# memory.net
KiCad netlist of a schematic drawn in Altium Designer
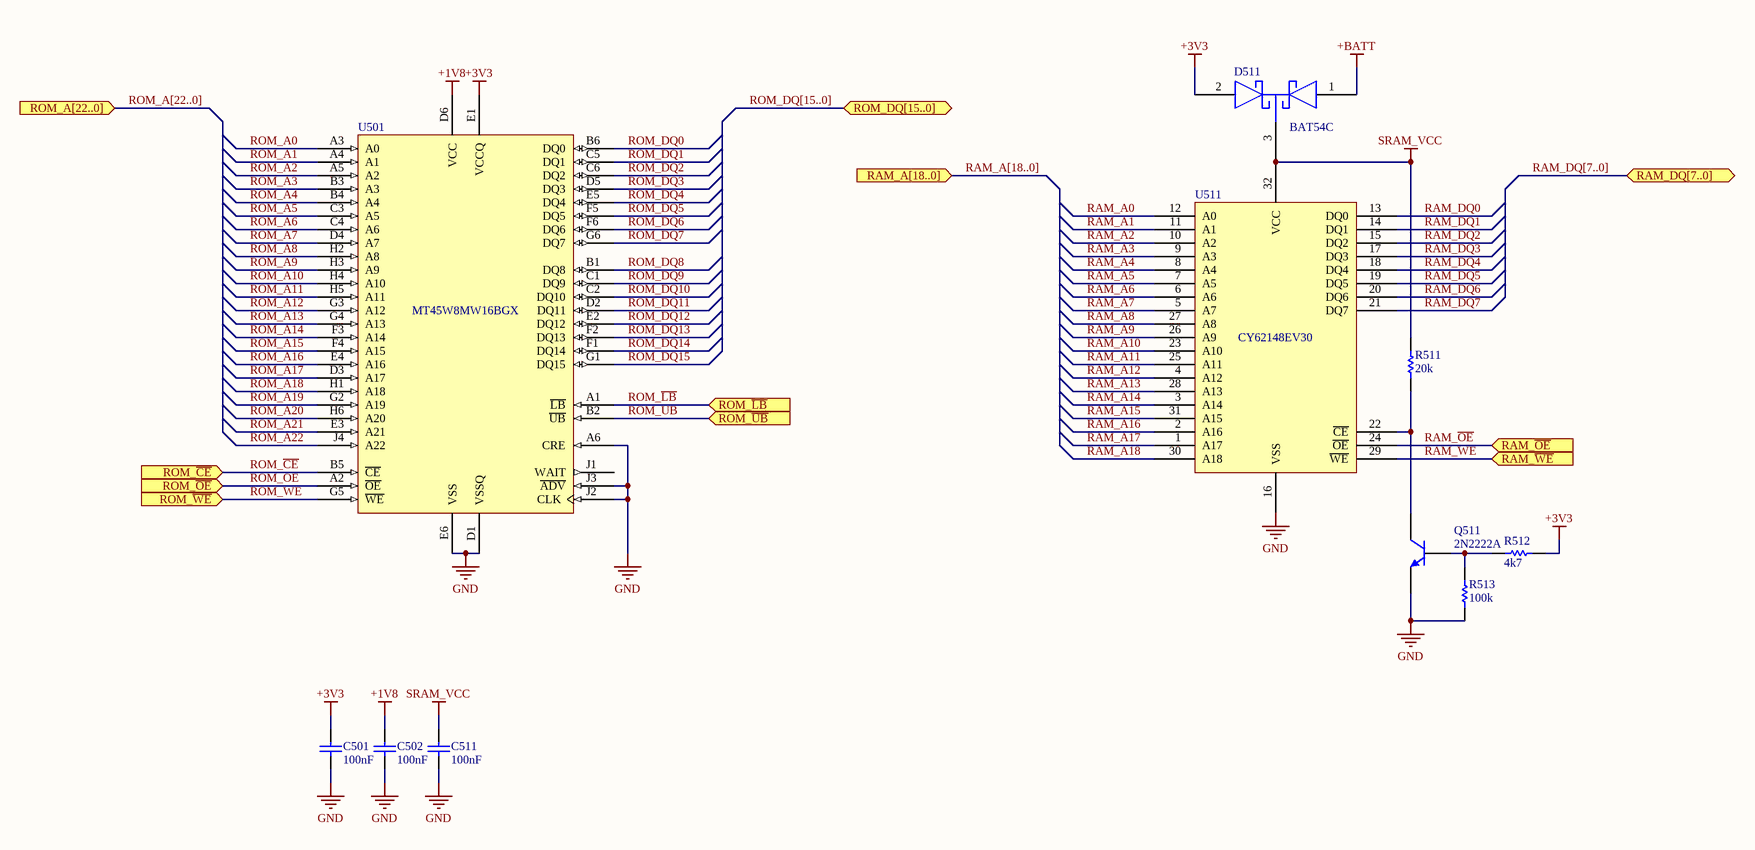
[diagram p0: memory.SchDoc]

(export (version "E")
  (design (tool "Eeschema 10.0.6"))
  (components
    (comp (ref "C501")
      (value "100nF")
      (footprint "SM0805")
      (description "Capacitor")
      (libsource (lib "Miscellaneous Devices") (part "Cap"))
    )
    (comp (ref "C502")
      (value "100nF")
      (footprint "SM0805")
      (description "Capacitor")
      (libsource (lib "Miscellaneous Devices") (part "Cap"))
    )
    (comp (ref "C511")
      (value "100nF")
      (footprint "SM0805")
      (description "Capacitor")
      (libsource (lib "Miscellaneous Devices") (part "Cap"))
    )
    (comp (ref "D511") (value "BAT54C") (footprint "SOT23EBC") (libsource (lib "Schlib1") (part "BAT54C")))
    (comp (ref "Q511")
      (value "2N2222A")
      (footprint "SOT23EBC")
      (description "NPN Transistor")
      (libsource (lib "Schlib1") (part "NPN"))
    )
    (comp (ref "R511")
      (value "20k")
      (footprint "SM0805")
      (description "Resistor")
      (libsource (lib "Miscellaneous Devices") (part "Res1"))
    )
    (comp (ref "R512")
      (value "4k7")
      (footprint "SM0805")
      (description "Resistor")
      (libsource (lib "Miscellaneous Devices") (part "Res1"))
    )
    (comp (ref "R513")
      (value "100k")
      (footprint "SM0805")
      (description "Resistor")
      (libsource (lib "Miscellaneous Devices") (part "Res1"))
    )
    (comp (ref "U501")
      (value "MT45W8MW16BGX")
      (footprint "VFBGA54")
      (libsource (lib "Schlib1") (part "MT45W8MW16BGX"))
    )
    (comp (ref "U511")
      (value "CY62148EV30")
      (footprint "TSOPII-32")
      (libsource (lib "Schlib1") (part "CY62148EV30"))
    )
  )
  (nets
    (net (code "1") (name "+1V8") (class "Default")
      (node (ref "C502") (pin "1") (pinfunction "1_1") (pintype "passive"))
      (node (ref "U501") (pin "D6") (pinfunction "VCC_D6") (pintype "power_in"))
    )
    (net (code "2") (name "+3V3") (class "Default")
      (node (ref "C501") (pin "1") (pinfunction "1_1") (pintype "passive"))
      (node (ref "D511") (pin "2") (pinfunction "2_2") (pintype "passive"))
      (node (ref "R512") (pin "2") (pinfunction "2_2") (pintype "passive"))
      (node (ref "U501") (pin "E1") (pinfunction "VCCQ_E1") (pintype "power_in"))
    )
    (net (code "3") (name "+BATT") (class "Default")
      (node (ref "D511") (pin "1") (pinfunction "1_1") (pintype "passive"))
    )
    (net (code "4") (name "/RAM_A0") (class "Default")
      (node (ref "U511") (pin "12") (pinfunction "A0_12") (pintype "passive"))
    )
    (net (code "5") (name "/RAM_A1") (class "Default")
      (node (ref "U511") (pin "11") (pinfunction "A1_11") (pintype "passive"))
    )
    (net (code "6") (name "/RAM_A2") (class "Default")
      (node (ref "U511") (pin "10") (pinfunction "A2_10") (pintype "passive"))
    )
    (net (code "7") (name "/RAM_A3") (class "Default")
      (node (ref "U511") (pin "9") (pinfunction "A3_9") (pintype "passive"))
    )
    (net (code "8") (name "/RAM_A4") (class "Default")
      (node (ref "U511") (pin "8") (pinfunction "A4_8") (pintype "passive"))
    )
    (net (code "9") (name "/RAM_A5") (class "Default")
      (node (ref "U511") (pin "7") (pinfunction "A5_7") (pintype "passive"))
    )
    (net (code "10") (name "/RAM_A6") (class "Default")
      (node (ref "U511") (pin "6") (pinfunction "A6_6") (pintype "passive"))
    )
    (net (code "11") (name "/RAM_A7") (class "Default")
      (node (ref "U511") (pin "5") (pinfunction "A7_5") (pintype "passive"))
    )
    (net (code "12") (name "/RAM_A8") (class "Default")
      (node (ref "U511") (pin "27") (pinfunction "A8_27") (pintype "passive"))
    )
    (net (code "13") (name "/RAM_A9") (class "Default")
      (node (ref "U511") (pin "26") (pinfunction "A9_26") (pintype "passive"))
    )
    (net (code "14") (name "/RAM_A10") (class "Default")
      (node (ref "U511") (pin "23") (pinfunction "A10_23") (pintype "passive"))
    )
    (net (code "15") (name "/RAM_A11") (class "Default")
      (node (ref "U511") (pin "25") (pinfunction "A11_25") (pintype "passive"))
    )
    (net (code "16") (name "/RAM_A12") (class "Default")
      (node (ref "U511") (pin "4") (pinfunction "A12_4") (pintype "passive"))
    )
    (net (code "17") (name "/RAM_A13") (class "Default")
      (node (ref "U511") (pin "28") (pinfunction "A13_28") (pintype "passive"))
    )
    (net (code "18") (name "/RAM_A14") (class "Default")
      (node (ref "U511") (pin "3") (pinfunction "A14_3") (pintype "passive"))
    )
    (net (code "19") (name "/RAM_A15") (class "Default")
      (node (ref "U511") (pin "31") (pinfunction "A15_31") (pintype "passive"))
    )
    (net (code "20") (name "/RAM_A16") (class "Default")
      (node (ref "U511") (pin "2") (pinfunction "A16_2") (pintype "passive"))
    )
    (net (code "21") (name "/RAM_A17") (class "Default")
      (node (ref "U511") (pin "1") (pinfunction "A17_1") (pintype "passive"))
    )
    (net (code "22") (name "/RAM_A18") (class "Default")
      (node (ref "U511") (pin "30") (pinfunction "A18_30") (pintype "passive"))
    )
    (net (code "24") (name "/RAM_DQ0") (class "Default")
      (node (ref "U511") (pin "13") (pinfunction "DQ0_13") (pintype "passive"))
    )
    (net (code "25") (name "/RAM_DQ1") (class "Default")
      (node (ref "U511") (pin "14") (pinfunction "DQ1_14") (pintype "passive"))
    )
    (net (code "26") (name "/RAM_DQ2") (class "Default")
      (node (ref "U511") (pin "15") (pinfunction "DQ2_15") (pintype "passive"))
    )
    (net (code "27") (name "/RAM_DQ3") (class "Default")
      (node (ref "U511") (pin "17") (pinfunction "DQ3_17") (pintype "passive"))
    )
    (net (code "28") (name "/RAM_DQ4") (class "Default")
      (node (ref "U511") (pin "18") (pinfunction "DQ4_18") (pintype "passive"))
    )
    (net (code "29") (name "/RAM_DQ5") (class "Default")
      (node (ref "U511") (pin "19") (pinfunction "DQ5_19") (pintype "passive"))
    )
    (net (code "30") (name "/RAM_DQ6") (class "Default")
      (node (ref "U511") (pin "20") (pinfunction "DQ6_20") (pintype "passive"))
    )
    (net (code "31") (name "/RAM_DQ7") (class "Default")
      (node (ref "U511") (pin "21") (pinfunction "DQ7_21") (pintype "passive"))
    )
    (net (code "33") (name "/RAM_~{OE}") (class "Default")
      (node (ref "U511") (pin "24") (pinfunction "~{OE}_24") (pintype "passive"))
    )
    (net (code "34") (name "/RAM_~{WE}") (class "Default")
      (node (ref "U511") (pin "29") (pinfunction "~{WE}_29") (pintype "passive"))
    )
    (net (code "35") (name "/ROM_A0") (class "Default")
      (node (ref "U501") (pin "A3") (pinfunction "A0_A3") (pintype "input"))
    )
    (net (code "36") (name "/ROM_A1") (class "Default")
      (node (ref "U501") (pin "A4") (pinfunction "A1_A4") (pintype "input"))
    )
    (net (code "37") (name "/ROM_A2") (class "Default")
      (node (ref "U501") (pin "A5") (pinfunction "A2_A5") (pintype "input"))
    )
    (net (code "38") (name "/ROM_A3") (class "Default")
      (node (ref "U501") (pin "B3") (pinfunction "A3_B3") (pintype "input"))
    )
    (net (code "39") (name "/ROM_A4") (class "Default")
      (node (ref "U501") (pin "B4") (pinfunction "A4_B4") (pintype "input"))
    )
    (net (code "40") (name "/ROM_A5") (class "Default")
      (node (ref "U501") (pin "C3") (pinfunction "A5_C3") (pintype "input"))
    )
    (net (code "41") (name "/ROM_A6") (class "Default")
      (node (ref "U501") (pin "C4") (pinfunction "A6_C4") (pintype "input"))
    )
    (net (code "42") (name "/ROM_A7") (class "Default")
      (node (ref "U501") (pin "D4") (pinfunction "A7_D4") (pintype "input"))
    )
    (net (code "43") (name "/ROM_A8") (class "Default")
      (node (ref "U501") (pin "H2") (pinfunction "A8_H2") (pintype "input"))
    )
    (net (code "44") (name "/ROM_A9") (class "Default")
      (node (ref "U501") (pin "H3") (pinfunction "A9_H3") (pintype "input"))
    )
    (net (code "45") (name "/ROM_A10") (class "Default")
      (node (ref "U501") (pin "H4") (pinfunction "A10_H4") (pintype "input"))
    )
    (net (code "46") (name "/ROM_A11") (class "Default")
      (node (ref "U501") (pin "H5") (pinfunction "A11_H5") (pintype "input"))
    )
    (net (code "47") (name "/ROM_A12") (class "Default")
      (node (ref "U501") (pin "G3") (pinfunction "A12_G3") (pintype "input"))
    )
    (net (code "48") (name "/ROM_A13") (class "Default")
      (node (ref "U501") (pin "G4") (pinfunction "A13_G4") (pintype "input"))
    )
    (net (code "49") (name "/ROM_A14") (class "Default")
      (node (ref "U501") (pin "F3") (pinfunction "A14_F3") (pintype "input"))
    )
    (net (code "50") (name "/ROM_A15") (class "Default")
      (node (ref "U501") (pin "F4") (pinfunction "A15_F4") (pintype "input"))
    )
    (net (code "51") (name "/ROM_A16") (class "Default")
      (node (ref "U501") (pin "E4") (pinfunction "A16_E4") (pintype "input"))
    )
    (net (code "52") (name "/ROM_A17") (class "Default")
      (node (ref "U501") (pin "D3") (pinfunction "A17_D3") (pintype "input"))
    )
    (net (code "53") (name "/ROM_A18") (class "Default")
      (node (ref "U501") (pin "H1") (pinfunction "A18_H1") (pintype "input"))
    )
    (net (code "54") (name "/ROM_A19") (class "Default")
      (node (ref "U501") (pin "G2") (pinfunction "A19_G2") (pintype "input"))
    )
    (net (code "55") (name "/ROM_A20") (class "Default")
      (node (ref "U501") (pin "H6") (pinfunction "A20_H6") (pintype "input"))
    )
    (net (code "56") (name "/ROM_A21") (class "Default")
      (node (ref "U501") (pin "E3") (pinfunction "A21_E3") (pintype "input"))
    )
    (net (code "57") (name "/ROM_A22") (class "Default")
      (node (ref "U501") (pin "J4") (pinfunction "A22_J4") (pintype "input"))
    )
    (net (code "59") (name "/ROM_DQ0") (class "Default")
      (node (ref "U501") (pin "B6") (pinfunction "DQ0_B6") (pintype "bidirectional"))
    )
    (net (code "60") (name "/ROM_DQ1") (class "Default")
      (node (ref "U501") (pin "C5") (pinfunction "DQ1_C5") (pintype "bidirectional"))
    )
    (net (code "61") (name "/ROM_DQ2") (class "Default")
      (node (ref "U501") (pin "C6") (pinfunction "DQ2_C6") (pintype "bidirectional"))
    )
    (net (code "62") (name "/ROM_DQ3") (class "Default")
      (node (ref "U501") (pin "D5") (pinfunction "DQ3_D5") (pintype "bidirectional"))
    )
    (net (code "63") (name "/ROM_DQ4") (class "Default")
      (node (ref "U501") (pin "E5") (pinfunction "DQ4_E5") (pintype "bidirectional"))
    )
    (net (code "64") (name "/ROM_DQ5") (class "Default")
      (node (ref "U501") (pin "F5") (pinfunction "DQ5_F5") (pintype "bidirectional"))
    )
    (net (code "65") (name "/ROM_DQ6") (class "Default")
      (node (ref "U501") (pin "F6") (pinfunction "DQ6_F6") (pintype "bidirectional"))
    )
    (net (code "66") (name "/ROM_DQ7") (class "Default")
      (node (ref "U501") (pin "G6") (pinfunction "DQ7_G6") (pintype "bidirectional"))
    )
    (net (code "67") (name "/ROM_DQ8") (class "Default")
      (node (ref "U501") (pin "B1") (pinfunction "DQ8_B1") (pintype "bidirectional"))
    )
    (net (code "68") (name "/ROM_DQ9") (class "Default")
      (node (ref "U501") (pin "C1") (pinfunction "DQ9_C1") (pintype "bidirectional"))
    )
    (net (code "69") (name "/ROM_DQ10") (class "Default")
      (node (ref "U501") (pin "C2") (pinfunction "DQ10_C2") (pintype "bidirectional"))
    )
    (net (code "70") (name "/ROM_DQ11") (class "Default")
      (node (ref "U501") (pin "D2") (pinfunction "DQ11_D2") (pintype "bidirectional"))
    )
    (net (code "71") (name "/ROM_DQ12") (class "Default")
      (node (ref "U501") (pin "E2") (pinfunction "DQ12_E2") (pintype "bidirectional"))
    )
    (net (code "72") (name "/ROM_DQ13") (class "Default")
      (node (ref "U501") (pin "F2") (pinfunction "DQ13_F2") (pintype "bidirectional"))
    )
    (net (code "73") (name "/ROM_DQ14") (class "Default")
      (node (ref "U501") (pin "F1") (pinfunction "DQ14_F1") (pintype "bidirectional"))
    )
    (net (code "74") (name "/ROM_DQ15") (class "Default")
      (node (ref "U501") (pin "G1") (pinfunction "DQ15_G1") (pintype "bidirectional"))
    )
    (net (code "76") (name "/ROM_~{CE}") (class "Default")
      (node (ref "U501") (pin "B5") (pinfunction "~{CE}_B5") (pintype "input"))
    )
    (net (code "77") (name "/ROM_~{LB}") (class "Default")
      (node (ref "U501") (pin "A1") (pinfunction "~{LB}_A1") (pintype "input"))
    )
    (net (code "78") (name "/ROM_~{OE}") (class "Default")
      (node (ref "U501") (pin "A2") (pinfunction "~{OE}_A2") (pintype "input"))
    )
    (net (code "79") (name "/ROM_~{UB}") (class "Default")
      (node (ref "U501") (pin "B2") (pinfunction "~{UB}_B2") (pintype "input"))
    )
    (net (code "80") (name "/ROM_~{WE}") (class "Default")
      (node (ref "U501") (pin "G5") (pinfunction "~{WE}_G5") (pintype "input"))
    )
    (net (code "81") (name "GND") (class "Default")
      (node (ref "C501") (pin "2") (pinfunction "2_2") (pintype "passive"))
      (node (ref "C502") (pin "2") (pinfunction "2_2") (pintype "passive"))
      (node (ref "C511") (pin "2") (pinfunction "2_2") (pintype "passive"))
      (node (ref "Q511") (pin "2") (pinfunction "E_2") (pintype "passive"))
      (node (ref "R513") (pin "2") (pinfunction "2_2") (pintype "passive"))
      (node (ref "U501") (pin "A6") (pinfunction "CRE_A6") (pintype "input"))
      (node (ref "U501") (pin "D1") (pinfunction "VSSQ_D1") (pintype "power_in"))
      (node (ref "U501") (pin "E6") (pinfunction "VSS_E6") (pintype "power_in"))
      (node (ref "U501") (pin "J2") (pinfunction "CLK_J2") (pintype "input"))
      (node (ref "U501") (pin "J3") (pinfunction "~{ADV}_J3") (pintype "input"))
      (node (ref "U511") (pin "16") (pinfunction "VSS_16") (pintype "passive"))
    )
    (net (code "82") (name "Net-(Q511-B)") (class "Default")
      (node (ref "Q511") (pin "1") (pinfunction "B_1") (pintype "passive"))
      (node (ref "R512") (pin "1") (pinfunction "1_1") (pintype "passive"))
      (node (ref "R513") (pin "1") (pinfunction "1_1") (pintype "passive"))
    )
    (net (code "83") (name "Net-(Q511-C)") (class "Default")
      (node (ref "Q511") (pin "3") (pinfunction "C_3") (pintype "passive"))
      (node (ref "R511") (pin "2") (pinfunction "2_2") (pintype "passive"))
      (node (ref "U511") (pin "22") (pinfunction "~{CE}_22") (pintype "passive"))
    )
    (net (code "84") (name "SRAM_VCC") (class "Default")
      (node (ref "C511") (pin "1") (pinfunction "1_1") (pintype "passive"))
      (node (ref "D511") (pin "3") (pinfunction "3_3") (pintype "passive"))
      (node (ref "R511") (pin "1") (pinfunction "1_1") (pintype "passive"))
      (node (ref "U511") (pin "32") (pinfunction "VCC_32") (pintype "passive"))
    )
    (net (code "85") (name "unconnected-(U501-WAIT-PadJ1)") (class "Default")
      (node (ref "U501") (pin "J1") (pinfunction "WAIT_J1") (pintype "output"))
    )
  )
)
